# me433.net
KiCad netlist of a schematic drawn in EAGLE
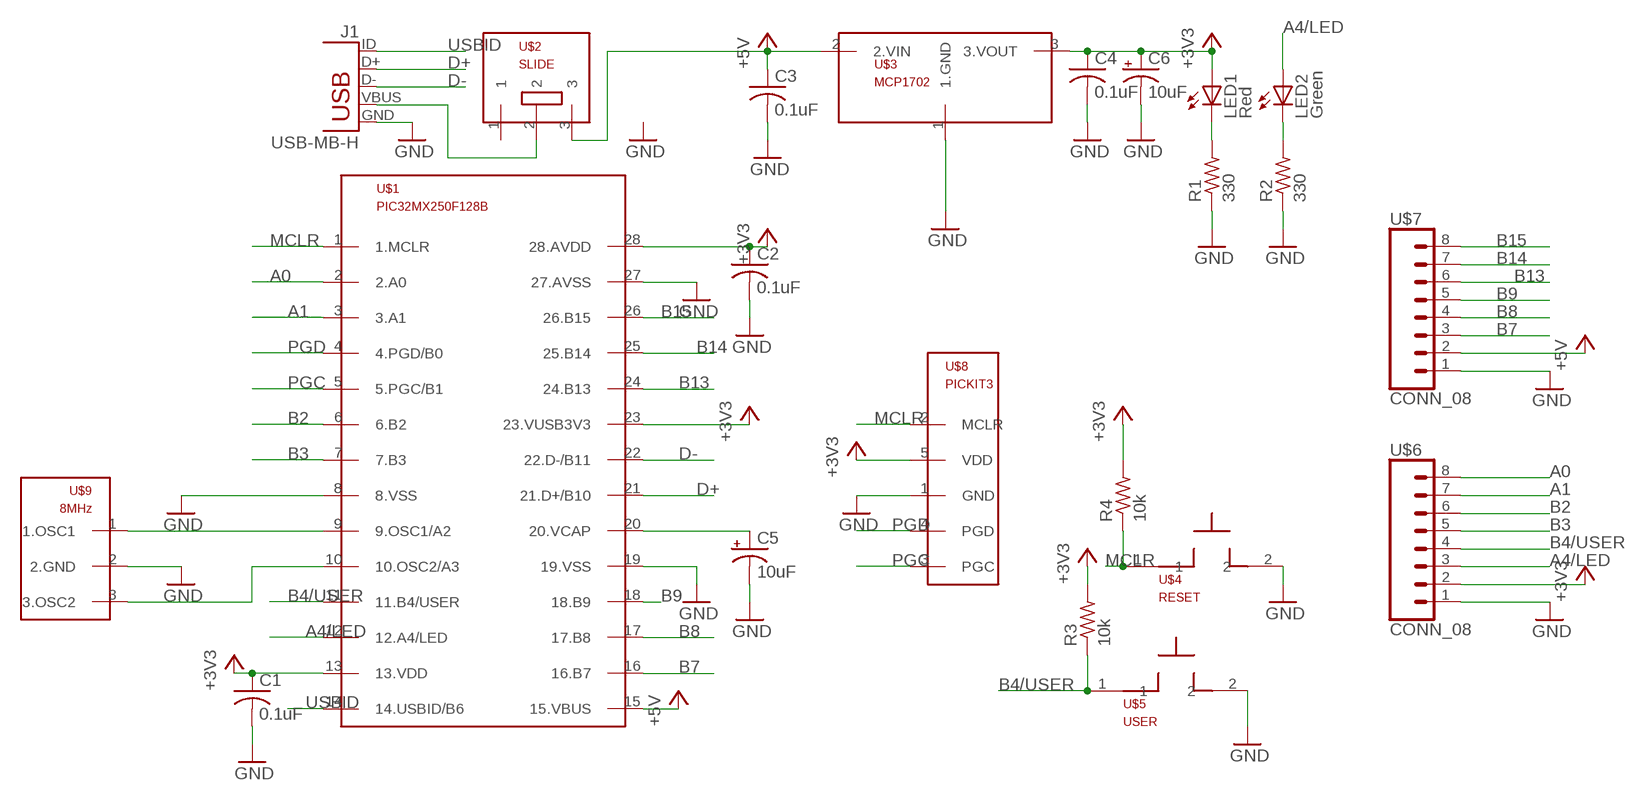
[diagram p0: schematic, sheet 1]

(export (version "E")
  (design (tool "Eeschema 10.0.6"))
  (components
    (comp (ref "C1")
      (value "0.1uF")
      (footprint "eagle-import:C025-025X050")
      (libsource (lib "eagle-import") (part "C-US025-025X050"))
    )
    (comp (ref "C2")
      (value "0.1uF")
      (footprint "eagle-import:C025-025X050")
      (libsource (lib "eagle-import") (part "C-US025-025X050"))
    )
    (comp (ref "C3")
      (value "0.1uF")
      (footprint "eagle-import:C025-025X050")
      (libsource (lib "eagle-import") (part "C-US025-025X050"))
    )
    (comp (ref "C4")
      (value "0.1uF")
      (footprint "eagle-import:C025-025X050")
      (libsource (lib "eagle-import") (part "C-US025-025X050"))
    )
    (comp (ref "C5")
      (value "10uF")
      (footprint "eagle-import:B45181B")
      (libsource (lib "eagle-import") (part "CPOL-USB45181B"))
    )
    (comp (ref "C6")
      (value "10uF")
      (footprint "eagle-import:B45181B")
      (libsource (lib "eagle-import") (part "CPOL-USB45181B"))
    )
    (comp (ref "J1")
      (value "USB-MB-H")
      (footprint "eagle-import:USB-MB-H")
      (libsource (lib "eagle-import") (part "USB-MB-H"))
    )
    (comp (ref "LED1")
      (value "Red")
      (footprint "eagle-import:LED3MM")
      (libsource (lib "eagle-import") (part "LED3MM"))
    )
    (comp (ref "LED2")
      (value "Green")
      (footprint "eagle-import:LED3MM")
      (libsource (lib "eagle-import") (part "LED3MM"))
    )
    (comp (ref "R1")
      (value "330")
      (footprint "eagle-import:0207_10")
      (libsource (lib "eagle-import") (part "R-US_0207/10"))
    )
    (comp (ref "R2")
      (value "330")
      (footprint "eagle-import:0207_10")
      (libsource (lib "eagle-import") (part "R-US_0207/10"))
    )
    (comp (ref "R3")
      (value "10k")
      (footprint "eagle-import:0207_10")
      (libsource (lib "eagle-import") (part "R-US_0207/10"))
    )
    (comp (ref "R4")
      (value "10k")
      (footprint "eagle-import:0207_10")
      (libsource (lib "eagle-import") (part "R-US_0207/10"))
    )
    (comp (ref "U$1")
      (value "PIC32MX250F128B")
      (footprint "eagle-import:DIL28-3")
      (libsource (lib "eagle-import") (part "PIC32MX250F128B"))
    )
    (comp (ref "U$2")
      (value "SLIDE")
      (footprint "eagle-import:SLIDE")
      (libsource (lib "eagle-import") (part "SLIDE"))
    )
    (comp (ref "U$3")
      (value "MCP1702")
      (footprint "eagle-import:TO92")
      (libsource (lib "eagle-import") (part "MCP1702"))
    )
    (comp (ref "U$4")
      (value "RESET")
      (footprint "eagle-import:PB")
      (libsource (lib "eagle-import") (part "PB"))
    )
    (comp (ref "U$5")
      (value "USER")
      (footprint "eagle-import:PB")
      (libsource (lib "eagle-import") (part "PB"))
    )
    (comp (ref "U$6")
      (value "CONN_08")
      (footprint "eagle-import:1X08")
      (libsource (lib "eagle-import") (part "CONN_08"))
    )
    (comp (ref "U$7")
      (value "CONN_08")
      (footprint "eagle-import:1X08")
      (libsource (lib "eagle-import") (part "CONN_08"))
    )
    (comp (ref "U$8")
      (value "PICKIT3")
      (footprint "eagle-import:1X05")
      (libsource (lib "eagle-import") (part "PICKIT3"))
    )
    (comp (ref "U$9")
      (value "8MHz")
      (footprint "eagle-import:OSC")
      (libsource (lib "eagle-import") (part "OSC"))
    )
  )
  (nets
    (net (code "1") (name "+3V3") (class "Default")
      (node (ref "C1") (pin "1") (pinfunction "1_1") (pintype "passive"))
      (node (ref "C2") (pin "1") (pinfunction "1_1") (pintype "passive"))
      (node (ref "C4") (pin "1") (pinfunction "1_1") (pintype "passive"))
      (node (ref "C6") (pin "+") (pinfunction "+_+") (pintype "passive"))
      (node (ref "LED1") (pin "A") (pinfunction "A_A") (pintype "passive"))
      (node (ref "R3") (pin "2") (pinfunction "2_2") (pintype "passive"))
      (node (ref "R4") (pin "2") (pinfunction "2_2") (pintype "passive"))
      (node (ref "U$1") (pin "13") (pinfunction "13.VDD_13") (pintype "bidirectional"))
      (node (ref "U$1") (pin "23") (pinfunction "23.VUSB3V3_23") (pintype "bidirectional"))
      (node (ref "U$1") (pin "28") (pinfunction "28.AVDD_28") (pintype "bidirectional"))
      (node (ref "U$3") (pin "3") (pinfunction "3.VOUT_3") (pintype "bidirectional"))
      (node (ref "U$6") (pin "2") (pinfunction "2_2") (pintype "passive"))
      (node (ref "U$8") (pin "5") (pinfunction "VDD_5") (pintype "bidirectional"))
    )
    (net (code "2") (name "+5V") (class "Default")
      (node (ref "C3") (pin "1") (pinfunction "1_1") (pintype "passive"))
      (node (ref "U$1") (pin "15") (pinfunction "15.VBUS_15") (pintype "bidirectional"))
      (node (ref "U$2") (pin "3") (pinfunction "3_3") (pintype "bidirectional"))
      (node (ref "U$3") (pin "2") (pinfunction "2.VIN_2") (pintype "bidirectional"))
      (node (ref "U$7") (pin "2") (pinfunction "2_2") (pintype "passive"))
    )
    (net (code "3") (name "/A0") (class "Default")
      (node (ref "U$1") (pin "2") (pinfunction "2.A0_2") (pintype "bidirectional"))
      (node (ref "U$6") (pin "8") (pinfunction "8_8") (pintype "passive"))
    )
    (net (code "4") (name "/A1") (class "Default")
      (node (ref "U$1") (pin "3") (pinfunction "3.A1_3") (pintype "bidirectional"))
      (node (ref "U$6") (pin "7") (pinfunction "7_7") (pintype "passive"))
    )
    (net (code "5") (name "/A4{slash}LED") (class "Default")
      (node (ref "LED2") (pin "A") (pinfunction "A_A") (pintype "passive"))
      (node (ref "U$1") (pin "12") (pinfunction "12.A4/LED_12") (pintype "bidirectional"))
      (node (ref "U$6") (pin "3") (pinfunction "3_3") (pintype "passive"))
    )
    (net (code "6") (name "/B2") (class "Default")
      (node (ref "U$1") (pin "6") (pinfunction "6.B2_6") (pintype "bidirectional"))
      (node (ref "U$6") (pin "6") (pinfunction "6_6") (pintype "passive"))
    )
    (net (code "7") (name "/B3") (class "Default")
      (node (ref "U$1") (pin "7") (pinfunction "7.B3_7") (pintype "bidirectional"))
      (node (ref "U$6") (pin "5") (pinfunction "5_5") (pintype "passive"))
    )
    (net (code "8") (name "/B4{slash}USER") (class "Default")
      (node (ref "R3") (pin "1") (pinfunction "1_1") (pintype "passive"))
      (node (ref "U$1") (pin "11") (pinfunction "11.B4/USER_11") (pintype "bidirectional"))
      (node (ref "U$5") (pin "1") (pinfunction "1_1") (pintype "bidirectional"))
      (node (ref "U$6") (pin "4") (pinfunction "4_4") (pintype "passive"))
    )
    (net (code "9") (name "/B7") (class "Default")
      (node (ref "U$1") (pin "16") (pinfunction "16.B7_16") (pintype "bidirectional"))
      (node (ref "U$7") (pin "3") (pinfunction "3_3") (pintype "passive"))
    )
    (net (code "10") (name "/B8") (class "Default")
      (node (ref "U$1") (pin "17") (pinfunction "17.B8_17") (pintype "bidirectional"))
      (node (ref "U$7") (pin "4") (pinfunction "4_4") (pintype "passive"))
    )
    (net (code "11") (name "/B9") (class "Default")
      (node (ref "U$1") (pin "18") (pinfunction "18.B9_18") (pintype "bidirectional"))
      (node (ref "U$7") (pin "5") (pinfunction "5_5") (pintype "passive"))
    )
    (net (code "12") (name "/B13") (class "Default")
      (node (ref "U$1") (pin "24") (pinfunction "24.B13_24") (pintype "bidirectional"))
      (node (ref "U$7") (pin "6") (pinfunction "6_6") (pintype "passive"))
    )
    (net (code "13") (name "/B14") (class "Default")
      (node (ref "U$1") (pin "25") (pinfunction "25.B14_25") (pintype "bidirectional"))
      (node (ref "U$7") (pin "7") (pinfunction "7_7") (pintype "passive"))
    )
    (net (code "14") (name "/B15") (class "Default")
      (node (ref "U$1") (pin "26") (pinfunction "26.B15_26") (pintype "bidirectional"))
      (node (ref "U$7") (pin "8") (pinfunction "8_8") (pintype "passive"))
    )
    (net (code "15") (name "/D+") (class "Default")
      (node (ref "J1") (pin "D+") (pinfunction "D+_D+") (pintype "bidirectional"))
      (node (ref "U$1") (pin "21") (pinfunction "21.D+/B10_21") (pintype "bidirectional"))
    )
    (net (code "16") (name "/D-") (class "Default")
      (node (ref "J1") (pin "D-") (pinfunction "D-_D-") (pintype "bidirectional"))
      (node (ref "U$1") (pin "22") (pinfunction "22.D-/B11_22") (pintype "bidirectional"))
    )
    (net (code "17") (name "/MCLR") (class "Default")
      (node (ref "R4") (pin "1") (pinfunction "1_1") (pintype "passive"))
      (node (ref "U$1") (pin "1") (pinfunction "1.MCLR_1") (pintype "bidirectional"))
      (node (ref "U$4") (pin "1") (pinfunction "1_1") (pintype "bidirectional"))
      (node (ref "U$8") (pin "2") (pinfunction "MCLR_2") (pintype "bidirectional"))
    )
    (net (code "18") (name "/PGC") (class "Default")
      (node (ref "U$1") (pin "5") (pinfunction "5.PGC/B1_5") (pintype "bidirectional"))
      (node (ref "U$8") (pin "3") (pinfunction "PGC_3") (pintype "bidirectional"))
    )
    (net (code "19") (name "/PGD") (class "Default")
      (node (ref "U$1") (pin "4") (pinfunction "4.PGD/B0_4") (pintype "bidirectional"))
      (node (ref "U$8") (pin "4") (pinfunction "PGD_4") (pintype "bidirectional"))
    )
    (net (code "20") (name "/USBID") (class "Default")
      (node (ref "J1") (pin "ID") (pinfunction "ID_ID") (pintype "bidirectional"))
      (node (ref "U$1") (pin "14") (pinfunction "14.USBID/B6_14") (pintype "bidirectional"))
    )
    (net (code "21") (name "GND") (class "Default")
      (node (ref "C1") (pin "2") (pinfunction "2_2") (pintype "passive"))
      (node (ref "C2") (pin "2") (pinfunction "2_2") (pintype "passive"))
      (node (ref "C3") (pin "2") (pinfunction "2_2") (pintype "passive"))
      (node (ref "C4") (pin "2") (pinfunction "2_2") (pintype "passive"))
      (node (ref "C5") (pin "-") (pinfunction "-_-") (pintype "passive"))
      (node (ref "C6") (pin "-") (pinfunction "-_-") (pintype "passive"))
      (node (ref "J1") (pin "GND") (pinfunction "GND_GND") (pintype "bidirectional"))
      (node (ref "R1") (pin "1") (pinfunction "1_1") (pintype "passive"))
      (node (ref "R2") (pin "1") (pinfunction "1_1") (pintype "passive"))
      (node (ref "U$1") (pin "19") (pinfunction "19.VSS_19") (pintype "bidirectional"))
      (node (ref "U$1") (pin "27") (pinfunction "27.AVSS_27") (pintype "bidirectional"))
      (node (ref "U$1") (pin "8") (pinfunction "8.VSS_8") (pintype "bidirectional"))
      (node (ref "U$3") (pin "1") (pinfunction "1.GND_1") (pintype "bidirectional"))
      (node (ref "U$4") (pin "2") (pinfunction "2_2") (pintype "bidirectional"))
      (node (ref "U$5") (pin "2") (pinfunction "2_2") (pintype "bidirectional"))
      (node (ref "U$6") (pin "1") (pinfunction "1_1") (pintype "passive"))
      (node (ref "U$7") (pin "1") (pinfunction "1_1") (pintype "passive"))
      (node (ref "U$8") (pin "1") (pinfunction "GND_1") (pintype "bidirectional"))
      (node (ref "U$9") (pin "2") (pinfunction "2.GND_2") (pintype "bidirectional"))
    )
    (net (code "22") (name "Net-(J1-PadVBUS)") (class "Default")
      (node (ref "J1") (pin "VBUS") (pinfunction "VBUS_VBUS") (pintype "bidirectional"))
      (node (ref "U$2") (pin "2") (pinfunction "2_2") (pintype "bidirectional"))
    )
    (net (code "23") (name "Net-(LED1-C)") (class "Default")
      (node (ref "LED1") (pin "K") (pinfunction "C_K") (pintype "passive"))
      (node (ref "R1") (pin "2") (pinfunction "2_2") (pintype "passive"))
    )
    (net (code "24") (name "Net-(LED2-C)") (class "Default")
      (node (ref "LED2") (pin "K") (pinfunction "C_K") (pintype "passive"))
      (node (ref "R2") (pin "2") (pinfunction "2_2") (pintype "passive"))
    )
    (net (code "25") (name "Net-(U$1-9.OSC1{slash}A2)") (class "Default")
      (node (ref "U$1") (pin "9") (pinfunction "9.OSC1/A2_9") (pintype "bidirectional"))
      (node (ref "U$9") (pin "1") (pinfunction "1.OSC1_1") (pintype "bidirectional"))
    )
    (net (code "26") (name "Net-(U$1-10.OSC2{slash}A3)") (class "Default")
      (node (ref "U$1") (pin "10") (pinfunction "10.OSC2/A3_10") (pintype "bidirectional"))
      (node (ref "U$9") (pin "3") (pinfunction "3.OSC2_3") (pintype "bidirectional"))
    )
    (net (code "27") (name "Net-(U$1-20.VCAP)") (class "Default")
      (node (ref "C5") (pin "+") (pinfunction "+_+") (pintype "passive"))
      (node (ref "U$1") (pin "20") (pinfunction "20.VCAP_20") (pintype "bidirectional"))
    )
    (net (code "28") (name "unconnected-(U$2-Pad1)") (class "Default")
      (node (ref "U$2") (pin "1") (pinfunction "1_1") (pintype "bidirectional"))
    )
  )
)
